# ActiTouch_Transmitter_Sheet1.net
KiCad netlist of a schematic drawn in Altium Designer
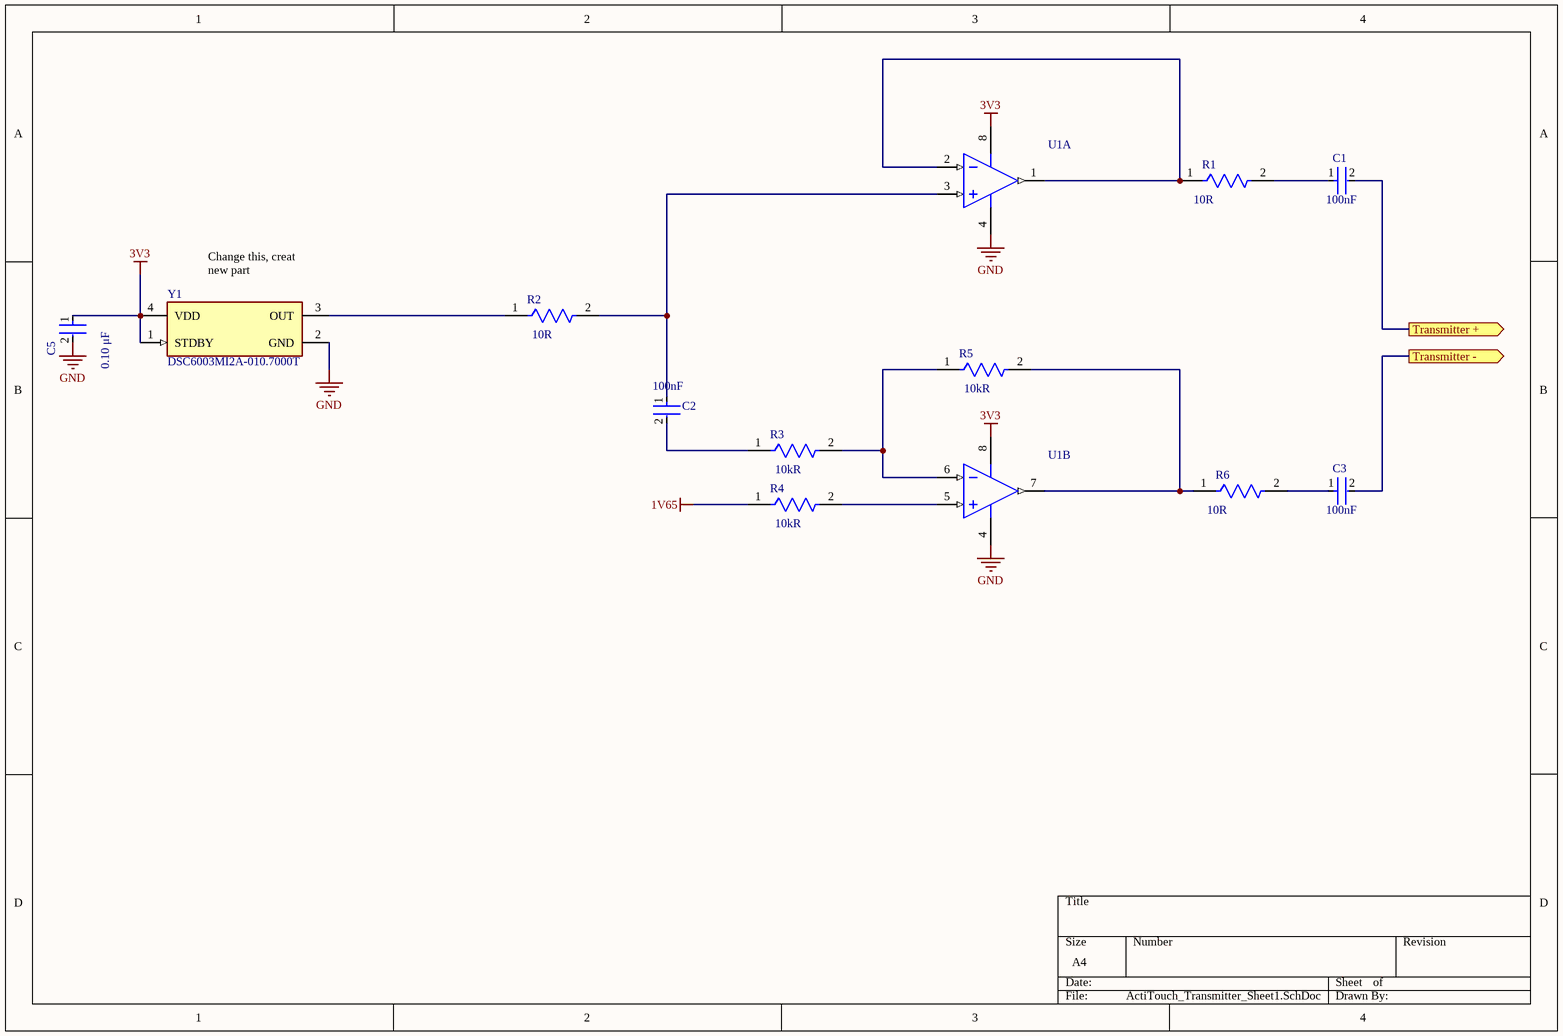
[diagram p0: ActiTouch_Transmitter_Sheet1.SchDoc]

(export (version "E")
  (design (tool "Eeschema 10.0.6"))
  (components
    (comp (ref "C1")
      (value "EMK107B7104KAHT")
      (footprint "FP-0603-L_1_6_0_1-W_0_8_0-IPC_B")
      (description "None")
      (fields (field (name "CAPACITANCE") "100nF") (field (name "TOLERANCE") "10%"))
      (libsource (lib "Altium Content Vault") (part "02cd4be3c70576c341d710602a673aa"))
    )
    (comp (ref "C2")
      (value "EMK107B7104KAHT")
      (footprint "FP-0603-L_1_6_0_1-W_0_8_0-IPC_B")
      (description "None")
      (fields (field (name "CAPACITANCE") "100nF") (field (name "TOLERANCE") "10%"))
      (libsource (lib "Altium Content Vault") (part "02cd4be3c70576c341d710602a673aa"))
    )
    (comp (ref "C3")
      (value "EMK107B7104KAHT")
      (footprint "FP-0603-L_1_6_0_1-W_0_8_0-IPC_B")
      (description "None")
      (fields (field (name "CAPACITANCE") "100nF") (field (name "TOLERANCE") "10%"))
      (libsource (lib "Altium Content Vault") (part "02cd4be3c70576c341d710602a673aa"))
    )
    (comp (ref "C5")
      (value "0.10 μF")
      (footprint "FP-C0603C-CF-MFG")
      (description "CAP CER 0.1UF 50V X7R 0603")
      (fields (field (name "TOLERANCE") "0.1") (field (name "MANUFACTURER") "KEMET"))
      (libsource (lib "Altium Content Vault") (part "b4654b650e69147ec39a6b967a45e02"))
    )
    (comp (ref "R1")
      (value "RNCP0603FTD10R0")
      (footprint "FP-RNCP0603-MFG")
      (description "10Ω ±1% 0.125W 0603 High Power Anti-Sulfur Thin Film Chip Resistor")
      (fields (field (name "TOLERANCE") "1%") (field (name "RESISTANCE") "10R"))
      (libsource (lib "Altium Content Vault") (part "1029c3af85768c4190bb7ad29bc67b5"))
    )
    (comp (ref "R2")
      (value "RNCP0603FTD10R0")
      (footprint "FP-RNCP0603-MFG")
      (description "10Ω ±1% 0.125W 0603 High Power Anti-Sulfur Thin Film Chip Resistor")
      (fields (field (name "TOLERANCE") "1%") (field (name "RESISTANCE") "10R"))
      (libsource (lib "Altium Content Vault") (part "1029c3af85768c4190bb7ad29bc67b5"))
    )
    (comp (ref "R3")
      (value "RNCP0603FTD10R0")
      (footprint "FP-RNCP0603-MFG")
      (description "10Ω ±1% 0.125W 0603 High Power Anti-Sulfur Thin Film Chip Resistor")
      (fields (field (name "TOLERANCE") "1%") (field (name "RESISTANCE") "10kR"))
      (libsource (lib "Altium Content Vault") (part "1029c3af85768c4190bb7ad29bc67b5"))
    )
    (comp (ref "R4")
      (value "RNCP0603FTD10R0")
      (footprint "FP-RNCP0603-MFG")
      (description "10Ω ±1% 0.125W 0603 High Power Anti-Sulfur Thin Film Chip Resistor")
      (fields (field (name "TOLERANCE") "1%") (field (name "RESISTANCE") "10kR"))
      (libsource (lib "Altium Content Vault") (part "1029c3af85768c4190bb7ad29bc67b5"))
    )
    (comp (ref "R5")
      (value "RNCP0603FTD10R0")
      (footprint "FP-RNCP0603-MFG")
      (description "10Ω ±1% 0.125W 0603 High Power Anti-Sulfur Thin Film Chip Resistor")
      (fields (field (name "TOLERANCE") "1%") (field (name "RESISTANCE") "10kR"))
      (libsource (lib "Altium Content Vault") (part "1029c3af85768c4190bb7ad29bc67b5"))
    )
    (comp (ref "R6")
      (value "RNCP0603FTD10R0")
      (footprint "FP-RNCP0603-MFG")
      (description "10Ω ±1% 0.125W 0603 High Power Anti-Sulfur Thin Film Chip Resistor")
      (fields (field (name "TOLERANCE") "1%") (field (name "RESISTANCE") "10R"))
      (libsource (lib "Altium Content Vault") (part "1029c3af85768c4190bb7ad29bc67b5"))
    )
    (comp (ref "U1")
      (value "OPA2836IDR")
      (footprint "D0008A_M")
      (fields (field (name "MANUFACTURER") "Texas Instruments"))
      (libsource (lib "Altium Content Vault") (part "TI-OPA2836D8"))
    )
    (comp (ref "Y1")
      (value "DSC6003MI2A-010.7000T")
      (footprint "FP-C04-1202-MFG")
      (libsource (lib "Altium Content Vault") (part "0879945b931ac6e5b4304121c4155e7"))
    )
  )
  (nets
    (net (code "1") (name "/Transmitter +") (class "Default")
      (node (ref "C1") (pin "2") (pinfunction "2_2") (pintype "passive"))
    )
    (net (code "2") (name "/Transmitter -") (class "Default")
      (node (ref "C3") (pin "2") (pinfunction "2_2") (pintype "passive"))
    )
    (net (code "3") (name "1V65") (class "Default")
      (node (ref "R4") (pin "1") (pinfunction "1_1") (pintype "passive"))
    )
    (net (code "4") (name "3V3") (class "Default")
      (node (ref "C5") (pin "1") (pinfunction "1_1") (pintype "passive"))
      (node (ref "U1") (pin "8") (pinfunction "VS+_8") (pintype "power_in"))
      (node (ref "Y1") (pin "1") (pinfunction "STDBY_1") (pintype "input"))
      (node (ref "Y1") (pin "4") (pinfunction "VDD_4") (pintype "power_in"))
    )
    (net (code "5") (name "GND") (class "Default")
      (node (ref "C5") (pin "2") (pinfunction "2_2") (pintype "passive"))
      (node (ref "U1") (pin "4") (pinfunction "VS-_4") (pintype "power_in"))
      (node (ref "Y1") (pin "2") (pinfunction "GND_2") (pintype "power_in"))
    )
    (net (code "6") (name "Net-(C1-Pad1)") (class "Default")
      (node (ref "C1") (pin "1") (pinfunction "1_1") (pintype "passive"))
      (node (ref "R1") (pin "2") (pinfunction "2_2") (pintype "passive"))
    )
    (net (code "7") (name "Net-(C2-Pad2)") (class "Default")
      (node (ref "C2") (pin "2") (pinfunction "2_2") (pintype "passive"))
      (node (ref "R3") (pin "1") (pinfunction "1_1") (pintype "passive"))
    )
    (net (code "8") (name "Net-(C3-Pad1)") (class "Default")
      (node (ref "C3") (pin "1") (pinfunction "1_1") (pintype "passive"))
      (node (ref "R6") (pin "2") (pinfunction "2_2") (pintype "passive"))
    )
    (net (code "9") (name "Net-(U1A-VIN1+)") (class "Default")
      (node (ref "C2") (pin "1") (pinfunction "1_1") (pintype "passive"))
      (node (ref "R2") (pin "2") (pinfunction "2_2") (pintype "passive"))
      (node (ref "U1") (pin "3") (pinfunction "VIN1+_3") (pintype "input"))
    )
    (net (code "10") (name "Net-(U1A-VIN1-)") (class "Default")
      (node (ref "R1") (pin "1") (pinfunction "1_1") (pintype "passive"))
      (node (ref "U1") (pin "1") (pinfunction "VOUT1_1") (pintype "output"))
      (node (ref "U1") (pin "2") (pinfunction "VIN1-_2") (pintype "input"))
    )
    (net (code "11") (name "Net-(U1B-VIN2+)") (class "Default")
      (node (ref "R4") (pin "2") (pinfunction "2_2") (pintype "passive"))
      (node (ref "U1") (pin "5") (pinfunction "VIN2+_5") (pintype "input"))
    )
    (net (code "12") (name "Net-(U1B-VIN2-)") (class "Default")
      (node (ref "R3") (pin "2") (pinfunction "2_2") (pintype "passive"))
      (node (ref "R5") (pin "1") (pinfunction "1_1") (pintype "passive"))
      (node (ref "U1") (pin "6") (pinfunction "VIN2-_6") (pintype "input"))
    )
    (net (code "13") (name "Net-(U1B-VOUT2)") (class "Default")
      (node (ref "R5") (pin "2") (pinfunction "2_2") (pintype "passive"))
      (node (ref "R6") (pin "1") (pinfunction "1_1") (pintype "passive"))
      (node (ref "U1") (pin "7") (pinfunction "VOUT2_7") (pintype "output"))
    )
    (net (code "14") (name "Net-(Y1-OUT)") (class "Default")
      (node (ref "R2") (pin "1") (pinfunction "1_1") (pintype "passive"))
      (node (ref "Y1") (pin "3") (pinfunction "OUT_3") (pintype "passive"))
    )
  )
)
